# BRD1001-003-320_-_Switchboard.net
KiCad netlist of a schematic drawn in EAGLE
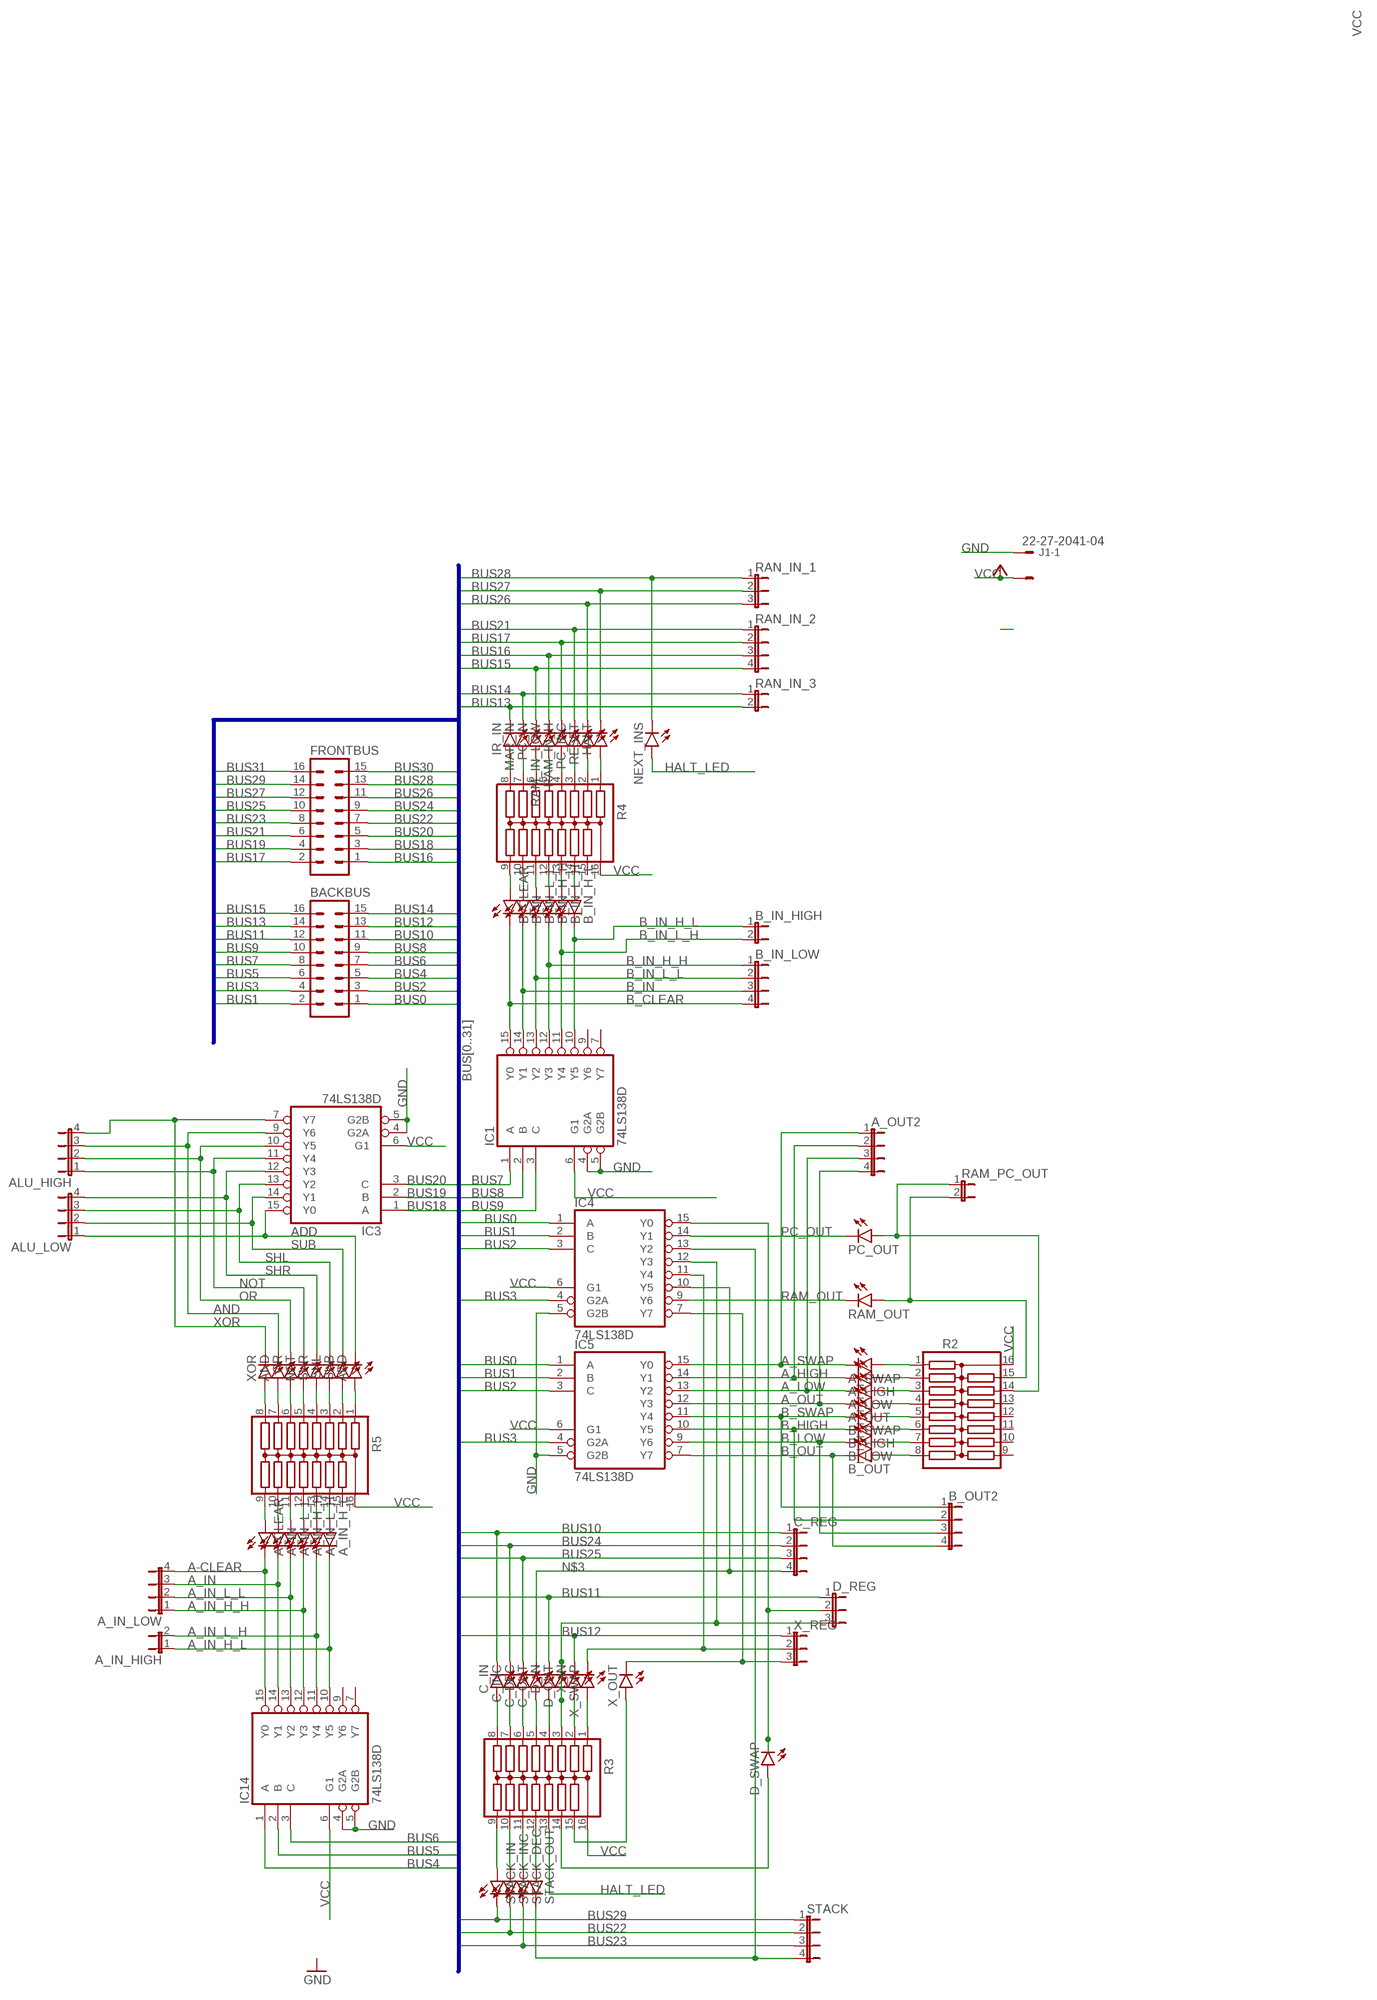
[diagram p0: schematic, sheet 1]

(export (version "E")
  (design (tool "Eeschema 10.0.6"))
  (components
    (comp (ref "ADD")
      (value "LEDSFH482")
      (footprint "eagle-import:SFH482")
      (libsource (lib "eagle-import") (part "LEDSFH482"))
    )
    (comp (ref "ALU_HIGH")
      (value "JP4E")
      (footprint "eagle-import:JP4")
      (libsource (lib "eagle-import") (part "JP4E"))
    )
    (comp (ref "ALU_LOW")
      (value "JP4E")
      (footprint "eagle-import:JP4")
      (libsource (lib "eagle-import") (part "JP4E"))
    )
    (comp (ref "AND")
      (value "LEDSFH482")
      (footprint "eagle-import:SFH482")
      (libsource (lib "eagle-import") (part "LEDSFH482"))
    )
    (comp (ref "A_CLEAR")
      (value "LEDSFH482")
      (footprint "eagle-import:SFH482")
      (libsource (lib "eagle-import") (part "LEDSFH482"))
    )
    (comp (ref "A_HIGH")
      (value "LEDSFH482")
      (footprint "eagle-import:SFH482")
      (libsource (lib "eagle-import") (part "LEDSFH482"))
    )
    (comp (ref "A_IN")
      (value "LEDSFH482")
      (footprint "eagle-import:SFH482")
      (libsource (lib "eagle-import") (part "LEDSFH482"))
    )
    (comp (ref "A_IN_HIGH")
      (value "JP1E")
      (footprint "eagle-import:JP1")
      (libsource (lib "eagle-import") (part "JP1E"))
    )
    (comp (ref "A_IN_H_H")
      (value "LEDSFH482")
      (footprint "eagle-import:SFH482")
      (libsource (lib "eagle-import") (part "LEDSFH482"))
    )
    (comp (ref "A_IN_H_L")
      (value "LEDSFH482")
      (footprint "eagle-import:SFH482")
      (libsource (lib "eagle-import") (part "LEDSFH482"))
    )
    (comp (ref "A_IN_LOW")
      (value "JP4E")
      (footprint "eagle-import:JP4")
      (libsource (lib "eagle-import") (part "JP4E"))
    )
    (comp (ref "A_IN_L_H")
      (value "LEDSFH482")
      (footprint "eagle-import:SFH482")
      (libsource (lib "eagle-import") (part "LEDSFH482"))
    )
    (comp (ref "A_IN_L_L")
      (value "LEDSFH482")
      (footprint "eagle-import:SFH482")
      (libsource (lib "eagle-import") (part "LEDSFH482"))
    )
    (comp (ref "A_LOW")
      (value "LEDSFH482")
      (footprint "eagle-import:SFH482")
      (libsource (lib "eagle-import") (part "LEDSFH482"))
    )
    (comp (ref "A_OUT")
      (value "LEDSFH482")
      (footprint "eagle-import:SFH482")
      (libsource (lib "eagle-import") (part "LEDSFH482"))
    )
    (comp (ref "A_OUT2")
      (value "JP4E")
      (footprint "eagle-import:JP4")
      (libsource (lib "eagle-import") (part "JP4E"))
    )
    (comp (ref "A_SWAP")
      (value "LEDSFH482")
      (footprint "eagle-import:SFH482")
      (libsource (lib "eagle-import") (part "LEDSFH482"))
    )
    (comp (ref "BACKBUS")
      (value "ML16")
      (footprint "eagle-import:ML16")
      (libsource (lib "eagle-import") (part "ML16"))
    )
    (comp (ref "B_CLEAR")
      (value "LEDSFH482")
      (footprint "eagle-import:SFH482")
      (libsource (lib "eagle-import") (part "LEDSFH482"))
    )
    (comp (ref "B_HIGH")
      (value "LEDSFH482")
      (footprint "eagle-import:SFH482")
      (libsource (lib "eagle-import") (part "LEDSFH482"))
    )
    (comp (ref "B_IN")
      (value "LEDSFH482")
      (footprint "eagle-import:SFH482")
      (libsource (lib "eagle-import") (part "LEDSFH482"))
    )
    (comp (ref "B_IN_HIGH")
      (value "JP1E")
      (footprint "eagle-import:JP1")
      (libsource (lib "eagle-import") (part "JP1E"))
    )
    (comp (ref "B_IN_H_H")
      (value "LEDSFH482")
      (footprint "eagle-import:SFH482")
      (libsource (lib "eagle-import") (part "LEDSFH482"))
    )
    (comp (ref "B_IN_H_L")
      (value "LEDSFH482")
      (footprint "eagle-import:SFH482")
      (libsource (lib "eagle-import") (part "LEDSFH482"))
    )
    (comp (ref "B_IN_LOW")
      (value "JP4E")
      (footprint "eagle-import:JP4")
      (libsource (lib "eagle-import") (part "JP4E"))
    )
    (comp (ref "B_IN_L_H")
      (value "LEDSFH482")
      (footprint "eagle-import:SFH482")
      (libsource (lib "eagle-import") (part "LEDSFH482"))
    )
    (comp (ref "B_IN_L_L")
      (value "LEDSFH482")
      (footprint "eagle-import:SFH482")
      (libsource (lib "eagle-import") (part "LEDSFH482"))
    )
    (comp (ref "B_LOW")
      (value "LEDSFH482")
      (footprint "eagle-import:SFH482")
      (libsource (lib "eagle-import") (part "LEDSFH482"))
    )
    (comp (ref "B_OUT")
      (value "LEDSFH482")
      (footprint "eagle-import:SFH482")
      (libsource (lib "eagle-import") (part "LEDSFH482"))
    )
    (comp (ref "B_OUT2")
      (value "JP4E")
      (footprint "eagle-import:JP4")
      (libsource (lib "eagle-import") (part "JP4E"))
    )
    (comp (ref "B_SWAP")
      (value "LEDSFH482")
      (footprint "eagle-import:SFH482")
      (libsource (lib "eagle-import") (part "LEDSFH482"))
    )
    (comp (ref "C_DEC")
      (value "LEDSFH482")
      (footprint "eagle-import:SFH482")
      (libsource (lib "eagle-import") (part "LEDSFH482"))
    )
    (comp (ref "C_IN")
      (value "LEDSFH482")
      (footprint "eagle-import:SFH482")
      (libsource (lib "eagle-import") (part "LEDSFH482"))
    )
    (comp (ref "C_INC")
      (value "LEDSFH482")
      (footprint "eagle-import:SFH482")
      (libsource (lib "eagle-import") (part "LEDSFH482"))
    )
    (comp (ref "C_OUT")
      (value "LEDSFH482")
      (footprint "eagle-import:SFH482")
      (libsource (lib "eagle-import") (part "LEDSFH482"))
    )
    (comp (ref "C_REG")
      (value "JP4E")
      (footprint "eagle-import:JP4")
      (libsource (lib "eagle-import") (part "JP4E"))
    )
    (comp (ref "D_IN")
      (value "LEDSFH482")
      (footprint "eagle-import:SFH482")
      (libsource (lib "eagle-import") (part "LEDSFH482"))
    )
    (comp (ref "D_OUT")
      (value "LEDSFH482")
      (footprint "eagle-import:SFH482")
      (libsource (lib "eagle-import") (part "LEDSFH482"))
    )
    (comp (ref "D_REG")
      (value "JP2W")
      (footprint "eagle-import:JP2W")
      (libsource (lib "eagle-import") (part "JP2W"))
    )
    (comp (ref "D_SWAP")
      (value "LEDSFH482")
      (footprint "eagle-import:SFH482")
      (libsource (lib "eagle-import") (part "LEDSFH482"))
    )
    (comp (ref "FRONTBUS")
      (value "ML16")
      (footprint "eagle-import:ML16")
      (libsource (lib "eagle-import") (part "ML16"))
    )
    (comp (ref "HALT")
      (value "LEDSFH482")
      (footprint "eagle-import:SFH482")
      (libsource (lib "eagle-import") (part "LEDSFH482"))
    )
    (comp (ref "IC1")
      (value "74LS138D")
      (footprint "eagle-import:SO16")
      (libsource (lib "eagle-import") (part "74138DLS"))
    )
    (comp (ref "IC3")
      (value "74LS138D")
      (footprint "eagle-import:SO16")
      (libsource (lib "eagle-import") (part "74138DLS"))
    )
    (comp (ref "IC4")
      (value "74LS138D")
      (footprint "eagle-import:SO16")
      (libsource (lib "eagle-import") (part "74138DLS"))
    )
    (comp (ref "IC5")
      (value "74LS138D")
      (footprint "eagle-import:SO16")
      (libsource (lib "eagle-import") (part "74138DLS"))
    )
    (comp (ref "IC14")
      (value "74LS138D")
      (footprint "eagle-import:SO16")
      (libsource (lib "eagle-import") (part "74138DLS"))
    )
    (comp (ref "IR_IN")
      (value "LEDSFH482")
      (footprint "eagle-import:SFH482")
      (libsource (lib "eagle-import") (part "LEDSFH482"))
    )
    (comp (ref "J1")
      (value "22-27-2041-04")
      (footprint "eagle-import:6410-04")
      (fields (field (name "MF") "MOLEX"))
      (libsource (lib "eagle-import") (part "22-?-0427-2041"))
    )
    (comp (ref "MAR_IN")
      (value "LEDSFH482")
      (footprint "eagle-import:SFH482")
      (libsource (lib "eagle-import") (part "LEDSFH482"))
    )
    (comp (ref "NEXT_INS")
      (value "LEDSFH482")
      (footprint "eagle-import:SFH482")
      (libsource (lib "eagle-import") (part "LEDSFH482"))
    )
    (comp (ref "NOT")
      (value "LEDSFH482")
      (footprint "eagle-import:SFH482")
      (libsource (lib "eagle-import") (part "LEDSFH482"))
    )
    (comp (ref "OR")
      (value "LEDSFH482")
      (footprint "eagle-import:SFH482")
      (libsource (lib "eagle-import") (part "LEDSFH482"))
    )
    (comp (ref "PC_IN")
      (value "LEDSFH482")
      (footprint "eagle-import:SFH482")
      (libsource (lib "eagle-import") (part "LEDSFH482"))
    )
    (comp (ref "PC_INC")
      (value "LEDSFH482")
      (footprint "eagle-import:SFH482")
      (libsource (lib "eagle-import") (part "LEDSFH482"))
    )
    (comp (ref "PC_OUT")
      (value "LEDSFH482")
      (footprint "eagle-import:SFH482")
      (libsource (lib "eagle-import") (part "LEDSFH482"))
    )
    (comp (ref "R2")
      (value "2NBS16-15")
      (footprint "eagle-import:SO16")
      (libsource (lib "eagle-import") (part "2NBS16-15"))
    )
    (comp (ref "R3")
      (value "2NBS16-15")
      (footprint "eagle-import:SO16")
      (libsource (lib "eagle-import") (part "2NBS16-15"))
    )
    (comp (ref "R4")
      (value "2NBS16-15")
      (footprint "eagle-import:SO16")
      (libsource (lib "eagle-import") (part "2NBS16-15"))
    )
    (comp (ref "R5")
      (value "2NBS16-15")
      (footprint "eagle-import:SO16")
      (libsource (lib "eagle-import") (part "2NBS16-15"))
    )
    (comp (ref "RAM_IN_H")
      (value "LEDSFH482")
      (footprint "eagle-import:SFH482")
      (libsource (lib "eagle-import") (part "LEDSFH482"))
    )
    (comp (ref "RAM_IN_LOW")
      (value "LEDSFH482")
      (footprint "eagle-import:SFH482")
      (libsource (lib "eagle-import") (part "LEDSFH482"))
    )
    (comp (ref "RAM_OUT")
      (value "LEDSFH482")
      (footprint "eagle-import:SFH482")
      (libsource (lib "eagle-import") (part "LEDSFH482"))
    )
    (comp (ref "RAM_PC_OUT")
      (value "JP1E")
      (footprint "eagle-import:JP1")
      (libsource (lib "eagle-import") (part "JP1E"))
    )
    (comp (ref "RAN_IN_1")
      (value "JP2W")
      (footprint "eagle-import:JP2W")
      (libsource (lib "eagle-import") (part "JP2W"))
    )
    (comp (ref "RAN_IN_2")
      (value "JP4E")
      (footprint "eagle-import:JP4")
      (libsource (lib "eagle-import") (part "JP4E"))
    )
    (comp (ref "RAN_IN_3")
      (value "JP1E")
      (footprint "eagle-import:JP1")
      (libsource (lib "eagle-import") (part "JP1E"))
    )
    (comp (ref "RESET")
      (value "LEDSFH482")
      (footprint "eagle-import:SFH482")
      (libsource (lib "eagle-import") (part "LEDSFH482"))
    )
    (comp (ref "SHL")
      (value "LEDSFH482")
      (footprint "eagle-import:SFH482")
      (libsource (lib "eagle-import") (part "LEDSFH482"))
    )
    (comp (ref "SHR")
      (value "LEDSFH482")
      (footprint "eagle-import:SFH482")
      (libsource (lib "eagle-import") (part "LEDSFH482"))
    )
    (comp (ref "STACK")
      (value "JP4E")
      (footprint "eagle-import:JP4")
      (libsource (lib "eagle-import") (part "JP4E"))
    )
    (comp (ref "STACK_DEC")
      (value "LEDSFH482")
      (footprint "eagle-import:SFH482")
      (libsource (lib "eagle-import") (part "LEDSFH482"))
    )
    (comp (ref "STACK_IN")
      (value "LEDSFH482")
      (footprint "eagle-import:SFH482")
      (libsource (lib "eagle-import") (part "LEDSFH482"))
    )
    (comp (ref "STACK_INC")
      (value "LEDSFH482")
      (footprint "eagle-import:SFH482")
      (libsource (lib "eagle-import") (part "LEDSFH482"))
    )
    (comp (ref "STACK_OUT")
      (value "LEDSFH482")
      (footprint "eagle-import:SFH482")
      (libsource (lib "eagle-import") (part "LEDSFH482"))
    )
    (comp (ref "SUB")
      (value "LEDSFH482")
      (footprint "eagle-import:SFH482")
      (libsource (lib "eagle-import") (part "LEDSFH482"))
    )
    (comp (ref "XOR")
      (value "LEDSFH482")
      (footprint "eagle-import:SFH482")
      (libsource (lib "eagle-import") (part "LEDSFH482"))
    )
    (comp (ref "X_IN")
      (value "LEDSFH482")
      (footprint "eagle-import:SFH482")
      (libsource (lib "eagle-import") (part "LEDSFH482"))
    )
    (comp (ref "X_OUT")
      (value "LEDSFH482")
      (footprint "eagle-import:SFH482")
      (libsource (lib "eagle-import") (part "LEDSFH482"))
    )
    (comp (ref "X_REG")
      (value "JP2W")
      (footprint "eagle-import:JP2W")
      (libsource (lib "eagle-import") (part "JP2W"))
    )
    (comp (ref "X_SWAP")
      (value "LEDSFH482")
      (footprint "eagle-import:SFH482")
      (libsource (lib "eagle-import") (part "LEDSFH482"))
    )
  )
  (nets
    (net (code "1") (name "/A-CLEAR") (class "Default")
      (node (ref "A_CLEAR") (pin "K") (pinfunction "C_K") (pintype "passive"))
      (node (ref "A_IN_LOW") (pin "4") (pinfunction "4_4") (pintype "passive"))
      (node (ref "IC14") (pin "15") (pinfunction "Y0_15") (pintype "output"))
    )
    (net (code "2") (name "/ADD") (class "Default")
      (node (ref "ADD") (pin "K") (pinfunction "C_K") (pintype "passive"))
      (node (ref "ALU_LOW") (pin "1") (pinfunction "1_1") (pintype "passive"))
      (node (ref "IC3") (pin "15") (pinfunction "Y0_15") (pintype "output"))
    )
    (net (code "3") (name "/AND") (class "Default")
      (node (ref "ALU_HIGH") (pin "3") (pinfunction "3_3") (pintype "passive"))
      (node (ref "AND") (pin "K") (pinfunction "C_K") (pintype "passive"))
      (node (ref "IC3") (pin "9") (pinfunction "Y6_9") (pintype "output"))
    )
    (net (code "4") (name "/A_HIGH") (class "Default")
      (node (ref "A_HIGH") (pin "K") (pinfunction "C_K") (pintype "passive"))
      (node (ref "A_OUT2") (pin "2") (pinfunction "2_2") (pintype "passive"))
      (node (ref "IC5") (pin "14") (pinfunction "Y1_14") (pintype "output"))
    )
    (net (code "5") (name "/A_IN") (class "Default")
      (node (ref "A_IN") (pin "K") (pinfunction "C_K") (pintype "passive"))
      (node (ref "A_IN_LOW") (pin "3") (pinfunction "3_3") (pintype "passive"))
      (node (ref "IC14") (pin "14") (pinfunction "Y1_14") (pintype "output"))
    )
    (net (code "6") (name "/A_IN_H_H") (class "Default")
      (node (ref "A_IN_H_H") (pin "K") (pinfunction "C_K") (pintype "passive"))
      (node (ref "A_IN_LOW") (pin "1") (pinfunction "1_1") (pintype "passive"))
      (node (ref "IC14") (pin "12") (pinfunction "Y3_12") (pintype "output"))
    )
    (net (code "7") (name "/A_IN_H_L") (class "Default")
      (node (ref "A_IN_HIGH") (pin "1") (pinfunction "1_1") (pintype "passive"))
      (node (ref "A_IN_H_L") (pin "K") (pinfunction "C_K") (pintype "passive"))
      (node (ref "IC14") (pin "10") (pinfunction "Y5_10") (pintype "output"))
    )
    (net (code "8") (name "/A_IN_L_H") (class "Default")
      (node (ref "A_IN_HIGH") (pin "2") (pinfunction "2_2") (pintype "passive"))
      (node (ref "A_IN_L_H") (pin "K") (pinfunction "C_K") (pintype "passive"))
      (node (ref "IC14") (pin "11") (pinfunction "Y4_11") (pintype "output"))
    )
    (net (code "9") (name "/A_IN_L_L") (class "Default")
      (node (ref "A_IN_LOW") (pin "2") (pinfunction "2_2") (pintype "passive"))
      (node (ref "A_IN_L_L") (pin "K") (pinfunction "C_K") (pintype "passive"))
      (node (ref "IC14") (pin "13") (pinfunction "Y2_13") (pintype "output"))
    )
    (net (code "10") (name "/A_LOW") (class "Default")
      (node (ref "A_LOW") (pin "K") (pinfunction "C_K") (pintype "passive"))
      (node (ref "A_OUT2") (pin "3") (pinfunction "3_3") (pintype "passive"))
      (node (ref "IC5") (pin "13") (pinfunction "Y2_13") (pintype "output"))
    )
    (net (code "11") (name "/A_OUT") (class "Default")
      (node (ref "A_OUT") (pin "K") (pinfunction "C_K") (pintype "passive"))
      (node (ref "A_OUT2") (pin "4") (pinfunction "4_4") (pintype "passive"))
      (node (ref "IC5") (pin "12") (pinfunction "Y3_12") (pintype "output"))
    )
    (net (code "12") (name "/A_SWAP") (class "Default")
      (node (ref "A_OUT2") (pin "1") (pinfunction "1_1") (pintype "passive"))
      (node (ref "A_SWAP") (pin "K") (pinfunction "C_K") (pintype "passive"))
      (node (ref "IC5") (pin "15") (pinfunction "Y0_15") (pintype "output"))
    )
    (net (code "13") (name "/BUS0") (class "Default")
      (node (ref "BACKBUS") (pin "1") (pinfunction "1_1") (pintype "passive"))
      (node (ref "IC4") (pin "1") (pinfunction "A_1") (pintype "input"))
      (node (ref "IC5") (pin "1") (pinfunction "A_1") (pintype "input"))
    )
    (net (code "14") (name "/BUS1") (class "Default")
      (node (ref "BACKBUS") (pin "2") (pinfunction "2_2") (pintype "passive"))
      (node (ref "IC4") (pin "2") (pinfunction "B_2") (pintype "input"))
      (node (ref "IC5") (pin "2") (pinfunction "B_2") (pintype "input"))
    )
    (net (code "15") (name "/BUS2") (class "Default")
      (node (ref "BACKBUS") (pin "3") (pinfunction "3_3") (pintype "passive"))
      (node (ref "IC4") (pin "3") (pinfunction "C_3") (pintype "input"))
      (node (ref "IC5") (pin "3") (pinfunction "C_3") (pintype "input"))
    )
    (net (code "16") (name "/BUS3") (class "Default")
      (node (ref "BACKBUS") (pin "4") (pinfunction "4_4") (pintype "passive"))
      (node (ref "IC4") (pin "4") (pinfunction "G2A_4") (pintype "input"))
      (node (ref "IC5") (pin "4") (pinfunction "G2A_4") (pintype "input"))
    )
    (net (code "17") (name "/BUS4") (class "Default")
      (node (ref "BACKBUS") (pin "5") (pinfunction "5_5") (pintype "passive"))
      (node (ref "IC14") (pin "1") (pinfunction "A_1") (pintype "input"))
    )
    (net (code "18") (name "/BUS5") (class "Default")
      (node (ref "BACKBUS") (pin "6") (pinfunction "6_6") (pintype "passive"))
      (node (ref "IC14") (pin "2") (pinfunction "B_2") (pintype "input"))
    )
    (net (code "19") (name "/BUS6") (class "Default")
      (node (ref "BACKBUS") (pin "7") (pinfunction "7_7") (pintype "passive"))
      (node (ref "IC14") (pin "3") (pinfunction "C_3") (pintype "input"))
    )
    (net (code "20") (name "/BUS7") (class "Default")
      (node (ref "BACKBUS") (pin "8") (pinfunction "8_8") (pintype "passive"))
      (node (ref "IC1") (pin "1") (pinfunction "A_1") (pintype "input"))
    )
    (net (code "21") (name "/BUS8") (class "Default")
      (node (ref "BACKBUS") (pin "9") (pinfunction "9_9") (pintype "passive"))
      (node (ref "IC1") (pin "2") (pinfunction "B_2") (pintype "input"))
    )
    (net (code "22") (name "/BUS9") (class "Default")
      (node (ref "BACKBUS") (pin "10") (pinfunction "10_10") (pintype "passive"))
      (node (ref "IC1") (pin "3") (pinfunction "C_3") (pintype "input"))
    )
    (net (code "23") (name "/BUS10") (class "Default")
      (node (ref "BACKBUS") (pin "11") (pinfunction "11_11") (pintype "passive"))
      (node (ref "C_IN") (pin "K") (pinfunction "C_K") (pintype "passive"))
      (node (ref "C_REG") (pin "1") (pinfunction "1_1") (pintype "passive"))
    )
    (net (code "24") (name "/BUS11") (class "Default")
      (node (ref "BACKBUS") (pin "12") (pinfunction "12_12") (pintype "passive"))
      (node (ref "D_IN") (pin "K") (pinfunction "C_K") (pintype "passive"))
      (node (ref "D_REG") (pin "1") (pinfunction "1_1") (pintype "passive"))
    )
    (net (code "25") (name "/BUS12") (class "Default")
      (node (ref "BACKBUS") (pin "13") (pinfunction "13_13") (pintype "passive"))
      (node (ref "X_IN") (pin "K") (pinfunction "C_K") (pintype "passive"))
      (node (ref "X_REG") (pin "1") (pinfunction "1_1") (pintype "passive"))
    )
    (net (code "26") (name "/BUS13") (class "Default")
      (node (ref "BACKBUS") (pin "14") (pinfunction "14_14") (pintype "passive"))
      (node (ref "IR_IN") (pin "K") (pinfunction "C_K") (pintype "passive"))
      (node (ref "RAN_IN_3") (pin "2") (pinfunction "2_2") (pintype "passive"))
    )
    (net (code "27") (name "/BUS14") (class "Default")
      (node (ref "BACKBUS") (pin "15") (pinfunction "15_15") (pintype "passive"))
      (node (ref "MAR_IN") (pin "K") (pinfunction "C_K") (pintype "passive"))
      (node (ref "RAN_IN_3") (pin "1") (pinfunction "1_1") (pintype "passive"))
    )
    (net (code "28") (name "/BUS15") (class "Default")
      (node (ref "BACKBUS") (pin "16") (pinfunction "16_16") (pintype "passive"))
      (node (ref "PC_IN") (pin "K") (pinfunction "C_K") (pintype "passive"))
      (node (ref "RAN_IN_2") (pin "4") (pinfunction "4_4") (pintype "passive"))
    )
    (net (code "29") (name "/BUS16") (class "Default")
      (node (ref "FRONTBUS") (pin "1") (pinfunction "1_1") (pintype "passive"))
      (node (ref "RAM_IN_LOW") (pin "K") (pinfunction "C_K") (pintype "passive"))
      (node (ref "RAN_IN_2") (pin "3") (pinfunction "3_3") (pintype "passive"))
    )
    (net (code "30") (name "/BUS17") (class "Default")
      (node (ref "FRONTBUS") (pin "2") (pinfunction "2_2") (pintype "passive"))
      (node (ref "RAM_IN_H") (pin "K") (pinfunction "C_K") (pintype "passive"))
      (node (ref "RAN_IN_2") (pin "2") (pinfunction "2_2") (pintype "passive"))
    )
    (net (code "31") (name "/BUS18") (class "Default")
      (node (ref "FRONTBUS") (pin "3") (pinfunction "3_3") (pintype "passive"))
      (node (ref "IC3") (pin "1") (pinfunction "A_1") (pintype "input"))
    )
    (net (code "32") (name "/BUS19") (class "Default")
      (node (ref "FRONTBUS") (pin "4") (pinfunction "4_4") (pintype "passive"))
      (node (ref "IC3") (pin "2") (pinfunction "B_2") (pintype "input"))
    )
    (net (code "33") (name "/BUS20") (class "Default")
      (node (ref "FRONTBUS") (pin "5") (pinfunction "5_5") (pintype "passive"))
      (node (ref "IC3") (pin "3") (pinfunction "C_3") (pintype "input"))
    )
    (net (code "34") (name "/BUS21") (class "Default")
      (node (ref "FRONTBUS") (pin "6") (pinfunction "6_6") (pintype "passive"))
      (node (ref "PC_INC") (pin "K") (pinfunction "C_K") (pintype "passive"))
      (node (ref "RAN_IN_2") (pin "1") (pinfunction "1_1") (pintype "passive"))
    )
    (net (code "35") (name "/BUS22") (class "Default")
      (node (ref "FRONTBUS") (pin "7") (pinfunction "7_7") (pintype "passive"))
      (node (ref "STACK") (pin "2") (pinfunction "2_2") (pintype "passive"))
      (node (ref "STACK_INC") (pin "K") (pinfunction "C_K") (pintype "passive"))
    )
    (net (code "36") (name "/BUS23") (class "Default")
      (node (ref "FRONTBUS") (pin "8") (pinfunction "8_8") (pintype "passive"))
      (node (ref "STACK") (pin "3") (pinfunction "3_3") (pintype "passive"))
      (node (ref "STACK_DEC") (pin "K") (pinfunction "C_K") (pintype "passive"))
    )
    (net (code "37") (name "/BUS24") (class "Default")
      (node (ref "C_INC") (pin "K") (pinfunction "C_K") (pintype "passive"))
      (node (ref "C_REG") (pin "2") (pinfunction "2_2") (pintype "passive"))
      (node (ref "FRONTBUS") (pin "9") (pinfunction "9_9") (pintype "passive"))
    )
    (net (code "38") (name "/BUS25") (class "Default")
      (node (ref "C_DEC") (pin "K") (pinfunction "C_K") (pintype "passive"))
      (node (ref "C_REG") (pin "3") (pinfunction "3_3") (pintype "passive"))
      (node (ref "FRONTBUS") (pin "10") (pinfunction "10_10") (pintype "passive"))
    )
    (net (code "39") (name "/BUS26") (class "Default")
      (node (ref "FRONTBUS") (pin "11") (pinfunction "11_11") (pintype "passive"))
      (node (ref "RAN_IN_1") (pin "3") (pinfunction "3_3") (pintype "passive"))
      (node (ref "RESET") (pin "K") (pinfunction "C_K") (pintype "passive"))
    )
    (net (code "40") (name "/BUS27") (class "Default")
      (node (ref "FRONTBUS") (pin "12") (pinfunction "12_12") (pintype "passive"))
      (node (ref "HALT") (pin "K") (pinfunction "C_K") (pintype "passive"))
      (node (ref "RAN_IN_1") (pin "2") (pinfunction "2_2") (pintype "passive"))
    )
    (net (code "41") (name "/BUS28") (class "Default")
      (node (ref "FRONTBUS") (pin "13") (pinfunction "13_13") (pintype "passive"))
      (node (ref "NEXT_INS") (pin "K") (pinfunction "C_K") (pintype "passive"))
      (node (ref "RAN_IN_1") (pin "1") (pinfunction "1_1") (pintype "passive"))
    )
    (net (code "42") (name "/BUS29") (class "Default")
      (node (ref "FRONTBUS") (pin "14") (pinfunction "14_14") (pintype "passive"))
      (node (ref "STACK") (pin "1") (pinfunction "1_1") (pintype "passive"))
      (node (ref "STACK_IN") (pin "K") (pinfunction "C_K") (pintype "passive"))
    )
    (net (code "43") (name "/BUS30") (class "Default")
      (node (ref "FRONTBUS") (pin "15") (pinfunction "15_15") (pintype "passive"))
    )
    (net (code "44") (name "/BUS31") (class "Default")
      (node (ref "FRONTBUS") (pin "16") (pinfunction "16_16") (pintype "passive"))
    )
    (net (code "46") (name "/B_CLEAR") (class "Default")
      (node (ref "B_CLEAR") (pin "K") (pinfunction "C_K") (pintype "passive"))
      (node (ref "B_IN_LOW") (pin "4") (pinfunction "4_4") (pintype "passive"))
      (node (ref "IC1") (pin "15") (pinfunction "Y0_15") (pintype "output"))
    )
    (net (code "47") (name "/B_HIGH") (class "Default")
      (node (ref "B_HIGH") (pin "K") (pinfunction "C_K") (pintype "passive"))
      (node (ref "B_OUT2") (pin "2") (pinfunction "2_2") (pintype "passive"))
      (node (ref "IC5") (pin "10") (pinfunction "Y5_10") (pintype "output"))
    )
    (net (code "48") (name "/B_IN") (class "Default")
      (node (ref "B_IN") (pin "K") (pinfunction "C_K") (pintype "passive"))
      (node (ref "B_IN_LOW") (pin "3") (pinfunction "3_3") (pintype "passive"))
      (node (ref "IC1") (pin "14") (pinfunction "Y1_14") (pintype "output"))
    )
    (net (code "49") (name "/B_IN_H_H") (class "Default")
      (node (ref "B_IN_H_H") (pin "K") (pinfunction "C_K") (pintype "passive"))
      (node (ref "B_IN_LOW") (pin "1") (pinfunction "1_1") (pintype "passive"))
      (node (ref "IC1") (pin "12") (pinfunction "Y3_12") (pintype "output"))
    )
    (net (code "50") (name "/B_IN_H_L") (class "Default")
      (node (ref "B_IN_HIGH") (pin "1") (pinfunction "1_1") (pintype "passive"))
      (node (ref "B_IN_H_L") (pin "K") (pinfunction "C_K") (pintype "passive"))
      (node (ref "IC1") (pin "10") (pinfunction "Y5_10") (pintype "output"))
    )
    (net (code "51") (name "/B_IN_L_H") (class "Default")
      (node (ref "B_IN_HIGH") (pin "2") (pinfunction "2_2") (pintype "passive"))
      (node (ref "B_IN_L_H") (pin "K") (pinfunction "C_K") (pintype "passive"))
      (node (ref "IC1") (pin "11") (pinfunction "Y4_11") (pintype "output"))
    )
    (net (code "52") (name "/B_IN_L_L") (class "Default")
      (node (ref "B_IN_LOW") (pin "2") (pinfunction "2_2") (pintype "passive"))
      (node (ref "B_IN_L_L") (pin "K") (pinfunction "C_K") (pintype "passive"))
      (node (ref "IC1") (pin "13") (pinfunction "Y2_13") (pintype "output"))
    )
    (net (code "53") (name "/B_LOW") (class "Default")
      (node (ref "B_LOW") (pin "K") (pinfunction "C_K") (pintype "passive"))
      (node (ref "B_OUT2") (pin "3") (pinfunction "3_3") (pintype "passive"))
      (node (ref "IC5") (pin "9") (pinfunction "Y6_9") (pintype "output"))
    )
    (net (code "54") (name "/B_OUT") (class "Default")
      (node (ref "B_OUT") (pin "K") (pinfunction "C_K") (pintype "passive"))
      (node (ref "B_OUT2") (pin "4") (pinfunction "4_4") (pintype "passive"))
      (node (ref "IC5") (pin "7") (pinfunction "Y7_7") (pintype "output"))
    )
    (net (code "55") (name "/B_SWAP") (class "Default")
      (node (ref "B_OUT2") (pin "1") (pinfunction "1_1") (pintype "passive"))
      (node (ref "B_SWAP") (pin "K") (pinfunction "C_K") (pintype "passive"))
      (node (ref "IC5") (pin "11") (pinfunction "Y4_11") (pintype "output"))
    )
    (net (code "56") (name "/HALT_LED") (class "Default")
      (node (ref "NEXT_INS") (pin "A") (pinfunction "A_A") (pintype "passive"))
      (node (ref "R3") (pin "13") (pinfunction "13_13") (pintype "passive"))
    )
    (net (code "57") (name "/N$3") (class "Default")
      (node (ref "C_OUT") (pin "K") (pinfunction "C_K") (pintype "passive"))
      (node (ref "C_REG") (pin "4") (pinfunction "4_4") (pintype "passive"))
      (node (ref "IC4") (pin "10") (pinfunction "Y5_10") (pintype "output"))
    )
    (net (code "58") (name "/NOT") (class "Default")
      (node (ref "ALU_HIGH") (pin "1") (pinfunction "1_1") (pintype "passive"))
      (node (ref "IC3") (pin "11") (pinfunction "Y4_11") (pintype "output"))
      (node (ref "NOT") (pin "K") (pinfunction "C_K") (pintype "passive"))
    )
    (net (code "59") (name "/OR") (class "Default")
      (node (ref "ALU_HIGH") (pin "2") (pinfunction "2_2") (pintype "passive"))
      (node (ref "IC3") (pin "10") (pinfunction "Y5_10") (pintype "output"))
      (node (ref "OR") (pin "K") (pinfunction "C_K") (pintype "passive"))
    )
    (net (code "60") (name "/PC_OUT") (class "Default")
      (node (ref "IC4") (pin "14") (pinfunction "Y1_14") (pintype "output"))
      (node (ref "PC_OUT") (pin "K") (pinfunction "C_K") (pintype "passive"))
    )
    (net (code "61") (name "/RAM_OUT") (class "Default")
      (node (ref "IC4") (pin "9") (pinfunction "Y6_9") (pintype "output"))
      (node (ref "RAM_OUT") (pin "K") (pinfunction "C_K") (pintype "passive"))
    )
    (net (code "62") (name "/SHL") (class "Default")
      (node (ref "ALU_LOW") (pin "3") (pinfunction "3_3") (pintype "passive"))
      (node (ref "IC3") (pin "13") (pinfunction "Y2_13") (pintype "output"))
      (node (ref "SHL") (pin "K") (pinfunction "C_K") (pintype "passive"))
    )
    (net (code "63") (name "/SHR") (class "Default")
      (node (ref "ALU_LOW") (pin "4") (pinfunction "4_4") (pintype "passive"))
      (node (ref "IC3") (pin "12") (pinfunction "Y3_12") (pintype "output"))
      (node (ref "SHR") (pin "K") (pinfunction "C_K") (pintype "passive"))
    )
    (net (code "64") (name "/SUB") (class "Default")
      (node (ref "ALU_LOW") (pin "2") (pinfunction "2_2") (pintype "passive"))
      (node (ref "IC3") (pin "14") (pinfunction "Y1_14") (pintype "output"))
      (node (ref "SUB") (pin "K") (pinfunction "C_K") (pintype "passive"))
    )
    (net (code "65") (name "/XOR") (class "Default")
      (node (ref "ALU_HIGH") (pin "4") (pinfunction "4_4") (pintype "passive"))
      (node (ref "IC3") (pin "7") (pinfunction "Y7_7") (pintype "output"))
      (node (ref "XOR") (pin "K") (pinfunction "C_K") (pintype "passive"))
    )
    (net (code "66") (name "GND") (class "Default")
      (node (ref "IC1") (pin "4") (pinfunction "G2A_4") (pintype "input"))
      (node (ref "IC1") (pin "5") (pinfunction "G2B_5") (pintype "input"))
      (node (ref "IC14") (pin "4") (pinfunction "G2A_4") (pintype "input"))
      (node (ref "IC14") (pin "5") (pinfunction "G2B_5") (pintype "input"))
      (node (ref "IC3") (pin "4") (pinfunction "G2A_4") (pintype "input"))
      (node (ref "IC3") (pin "5") (pinfunction "G2B_5") (pintype "input"))
      (node (ref "IC4") (pin "5") (pinfunction "G2B_5") (pintype "input"))
      (node (ref "IC5") (pin "5") (pinfunction "G2B_5") (pintype "input"))
      (node (ref "J1") (pin "1") (pinfunction "S_1") (pintype "passive"))
    )
    (net (code "67") (name "Net-(ADD-PadA)") (class "Default")
      (node (ref "ADD") (pin "A") (pinfunction "A_A") (pintype "passive"))
      (node (ref "R5") (pin "1") (pinfunction "1_1") (pintype "passive"))
    )
    (net (code "68") (name "Net-(AND-PadA)") (class "Default")
      (node (ref "AND") (pin "A") (pinfunction "A_A") (pintype "passive"))
      (node (ref "R5") (pin "7") (pinfunction "7_7") (pintype "passive"))
    )
    (net (code "69") (name "Net-(A_CLEAR-PadA)") (class "Default")
      (node (ref "A_CLEAR") (pin "A") (pinfunction "A_A") (pintype "passive"))
      (node (ref "R5") (pin "9") (pinfunction "9_9") (pintype "passive"))
    )
    (net (code "70") (name "Net-(A_HIGH-PadA)") (class "Default")
      (node (ref "A_HIGH") (pin "A") (pinfunction "A_A") (pintype "passive"))
      (node (ref "R2") (pin "2") (pinfunction "2_2") (pintype "passive"))
    )
    (net (code "71") (name "Net-(A_IN-PadA)") (class "Default")
      (node (ref "A_IN") (pin "A") (pinfunction "A_A") (pintype "passive"))
      (node (ref "R5") (pin "10") (pinfunction "10_10") (pintype "passive"))
    )
    (net (code "72") (name "Net-(A_IN_H_H-PadA)") (class "Default")
      (node (ref "A_IN_H_H") (pin "A") (pinfunction "A_A") (pintype "passive"))
      (node (ref "R5") (pin "12") (pinfunction "12_12") (pintype "passive"))
    )
    (net (code "73") (name "Net-(A_IN_H_L-PadA)") (class "Default")
      (node (ref "A_IN_H_L") (pin "A") (pinfunction "A_A") (pintype "passive"))
      (node (ref "R5") (pin "14") (pinfunction "14_14") (pintype "passive"))
    )
    (net (code "74") (name "Net-(A_IN_L_H-PadA)") (class "Default")
      (node (ref "A_IN_L_H") (pin "A") (pinfunction "A_A") (pintype "passive"))
      (node (ref "R5") (pin "13") (pinfunction "13_13") (pintype "passive"))
    )
    (net (code "75") (name "Net-(A_IN_L_L-PadA)") (class "Default")
      (node (ref "A_IN_L_L") (pin "A") (pinfunction "A_A") (pintype "passive"))
      (node (ref "R5") (pin "11") (pinfunction "11_11") (pintype "passive"))
    )
    (net (code "76") (name "Net-(A_LOW-PadA)") (class "Default")
      (node (ref "A_LOW") (pin "A") (pinfunction "A_A") (pintype "passive"))
      (node (ref "R2") (pin "3") (pinfunction "3_3") (pintype "passive"))
    )
    (net (code "77") (name "Net-(A_OUT-PadA)") (class "Default")
      (node (ref "A_OUT") (pin "A") (pinfunction "A_A") (pintype "passive"))
      (node (ref "R2") (pin "4") (pinfunction "4_4") (pintype "passive"))
    )
    (net (code "78") (name "Net-(A_SWAP-PadA)") (class "Default")
      (node (ref "A_SWAP") (pin "A") (pinfunction "A_A") (pintype "passive"))
      (node (ref "R2") (pin "1") (pinfunction "1_1") (pintype "passive"))
    )
    (net (code "79") (name "Net-(B_CLEAR-PadA)") (class "Default")
      (node (ref "B_CLEAR") (pin "A") (pinfunction "A_A") (pintype "passive"))
      (node (ref "R4") (pin "9") (pinfunction "9_9") (pintype "passive"))
    )
    (net (code "80") (name "Net-(B_HIGH-PadA)") (class "Default")
      (node (ref "B_HIGH") (pin "A") (pinfunction "A_A") (pintype "passive"))
      (node (ref "R2") (pin "6") (pinfunction "6_6") (pintype "passive"))
    )
    (net (code "81") (name "Net-(B_IN-PadA)") (class "Default")
      (node (ref "B_IN") (pin "A") (pinfunction "A_A") (pintype "passive"))
      (node (ref "R4") (pin "10") (pinfunction "10_10") (pintype "passive"))
    )
    (net (code "82") (name "Net-(B_IN_H_H-PadA)") (class "Default")
      (node (ref "B_IN_H_H") (pin "A") (pinfunction "A_A") (pintype "passive"))
      (node (ref "R4") (pin "12") (pinfunction "12_12") (pintype "passive"))
    )
    (net (code "83") (name "Net-(B_IN_H_L-PadA)") (class "Default")
      (node (ref "B_IN_H_L") (pin "A") (pinfunction "A_A") (pintype "passive"))
      (node (ref "R4") (pin "14") (pinfunction "14_14") (pintype "passive"))
    )
    (net (code "84") (name "Net-(B_IN_L_H-PadA)") (class "Default")
      (node (ref "B_IN_L_H") (pin "A") (pinfunction "A_A") (pintype "passive"))
      (node (ref "R4") (pin "13") (pinfunction "13_13") (pintype "passive"))
    )
    (net (code "85") (name "Net-(B_IN_L_L-PadA)") (class "Default")
      (node (ref "B_IN_L_L") (pin "A") (pinfunction "A_A") (pintype "passive"))
      (node (ref "R4") (pin "11") (pinfunction "11_11") (pintype "passive"))
    )
    (net (code "86") (name "Net-(B_LOW-PadA)") (class "Default")
      (node (ref "B_LOW") (pin "A") (pinfunction "A_A") (pintype "passive"))
      (node (ref "R2") (pin "7") (pinfunction "7_7") (pintype "passive"))
    )
    (net (code "87") (name "Net-(B_OUT-PadA)") (class "Default")
      (node (ref "B_OUT") (pin "A") (pinfunction "A_A") (pintype "passive"))
      (node (ref "R2") (pin "8") (pinfunction "8_8") (pintype "passive"))
    )
    (net (code "88") (name "Net-(B_SWAP-PadA)") (class "Default")
      (node (ref "B_SWAP") (pin "A") (pinfunction "A_A") (pintype "passive"))
      (node (ref "R2") (pin "5") (pinfunction "5_5") (pintype "passive"))
    )
    (net (code "89") (name "Net-(C_DEC-PadA)") (class "Default")
      (node (ref "C_DEC") (pin "A") (pinfunction "A_A") (pintype "passive"))
      (node (ref "R3") (pin "6") (pinfunction "6_6") (pintype "passive"))
    )
    (net (code "90") (name "Net-(C_IN-PadA)") (class "Default")
      (node (ref "C_IN") (pin "A") (pinfunction "A_A") (pintype "passive"))
      (node (ref "R3") (pin "8") (pinfunction "8_8") (pintype "passive"))
    )
    (net (code "91") (name "Net-(C_INC-PadA)") (class "Default")
      (node (ref "C_INC") (pin "A") (pinfunction "A_A") (pintype "passive"))
      (node (ref "R3") (pin "7") (pinfunction "7_7") (pintype "passive"))
    )
    (net (code "92") (name "Net-(C_OUT-PadA)") (class "Default")
      (node (ref "C_OUT") (pin "A") (pinfunction "A_A") (pintype "passive"))
      (node (ref "R3") (pin "5") (pinfunction "5_5") (pintype "passive"))
    )
    (net (code "93") (name "Net-(D_IN-PadA)") (class "Default")
      (node (ref "D_IN") (pin "A") (pinfunction "A_A") (pintype "passive"))
      (node (ref "R3") (pin "4") (pinfunction "4_4") (pintype "passive"))
    )
    (net (code "94") (name "Net-(D_OUT-C)") (class "Default")
      (node (ref "D_OUT") (pin "A") (pinfunction "A_A") (pintype "passive"))
      (node (ref "D_OUT") (pin "K") (pinfunction "C_K") (pintype "passive"))
      (node (ref "D_REG") (pin "3") (pinfunction "3_3") (pintype "passive"))
      (node (ref "IC4") (pin "12") (pinfunction "Y3_12") (pintype "output"))
      (node (ref "R3") (pin "3") (pinfunction "3_3") (pintype "passive"))
    )
    (net (code "95") (name "Net-(D_SWAP-C)") (class "Default")
      (node (ref "D_REG") (pin "2") (pinfunction "2_2") (pintype "passive"))
      (node (ref "D_SWAP") (pin "K") (pinfunction "C_K") (pintype "passive"))
      (node (ref "IC4") (pin "15") (pinfunction "Y0_15") (pintype "output"))
    )
    (net (code "96") (name "Net-(D_SWAP-PadA)") (class "Default")
      (node (ref "D_SWAP") (pin "A") (pinfunction "A_A") (pintype "passive"))
      (node (ref "R3") (pin "14") (pinfunction "14_14") (pintype "passive"))
    )
    (net (code "97") (name "Net-(HALT-PadA)") (class "Default")
      (node (ref "HALT") (pin "A") (pinfunction "A_A") (pintype "passive"))
      (node (ref "R4") (pin "1") (pinfunction "1_1") (pintype "passive"))
    )
    (net (code "98") (name "Net-(IC4A-Y2)") (class "Default")
      (node (ref "IC4") (pin "13") (pinfunction "Y2_13") (pintype "output"))
      (node (ref "STACK") (pin "4") (pinfunction "4_4") (pintype "passive"))
      (node (ref "STACK_OUT") (pin "K") (pinfunction "C_K") (pintype "passive"))
    )
    (net (code "99") (name "Net-(IC4A-Y4)") (class "Default")
      (node (ref "IC4") (pin "11") (pinfunction "Y4_11") (pintype "output"))
      (node (ref "X_REG") (pin "2") (pinfunction "2_2") (pintype "passive"))
      (node (ref "X_SWAP") (pin "K") (pinfunction "C_K") (pintype "passive"))
    )
    (net (code "100") (name "Net-(IC4A-Y7)") (class "Default")
      (node (ref "IC4") (pin "7") (pinfunction "Y7_7") (pintype "output"))
      (node (ref "X_OUT") (pin "K") (pinfunction "C_K") (pintype "passive"))
      (node (ref "X_REG") (pin "3") (pinfunction "3_3") (pintype "passive"))
    )
    (net (code "101") (name "Net-(IR_IN-PadA)") (class "Default")
      (node (ref "IR_IN") (pin "A") (pinfunction "A_A") (pintype "passive"))
      (node (ref "R4") (pin "8") (pinfunction "8_8") (pintype "passive"))
    )
    (net (code "102") (name "Net-(MAR_IN-PadA)") (class "Default")
      (node (ref "MAR_IN") (pin "A") (pinfunction "A_A") (pintype "passive"))
      (node (ref "R4") (pin "7") (pinfunction "7_7") (pintype "passive"))
    )
    (net (code "103") (name "Net-(NOT-PadA)") (class "Default")
      (node (ref "NOT") (pin "A") (pinfunction "A_A") (pintype "passive"))
      (node (ref "R5") (pin "5") (pinfunction "5_5") (pintype "passive"))
    )
    (net (code "104") (name "Net-(OR-PadA)") (class "Default")
      (node (ref "OR") (pin "A") (pinfunction "A_A") (pintype "passive"))
      (node (ref "R5") (pin "6") (pinfunction "6_6") (pintype "passive"))
    )
    (net (code "105") (name "Net-(PC_IN-PadA)") (class "Default")
      (node (ref "PC_IN") (pin "A") (pinfunction "A_A") (pintype "passive"))
      (node (ref "R4") (pin "6") (pinfunction "6_6") (pintype "passive"))
    )
    (net (code "106") (name "Net-(PC_INC-PadA)") (class "Default")
      (node (ref "PC_INC") (pin "A") (pinfunction "A_A") (pintype "passive"))
      (node (ref "R4") (pin "3") (pinfunction "3_3") (pintype "passive"))
    )
    (net (code "107") (name "Net-(PC_OUT-PadA)") (class "Default")
      (node (ref "PC_OUT") (pin "A") (pinfunction "A_A") (pintype "passive"))
      (node (ref "R2") (pin "14") (pinfunction "14_14") (pintype "passive"))
      (node (ref "RAM_PC_OUT") (pin "1") (pinfunction "1_1") (pintype "passive"))
    )
    (net (code "108") (name "Net-(R2-Pad15)") (class "Default")
      (node (ref "R2") (pin "15") (pinfunction "15_15") (pintype "passive"))
      (node (ref "RAM_OUT") (pin "A") (pinfunction "A_A") (pintype "passive"))
      (node (ref "RAM_PC_OUT") (pin "2") (pinfunction "2_2") (pintype "passive"))
    )
    (net (code "109") (name "Net-(R3-Pad1)") (class "Default")
      (node (ref "R3") (pin "1") (pinfunction "1_1") (pintype "passive"))
      (node (ref "X_SWAP") (pin "A") (pinfunction "A_A") (pintype "passive"))
    )
    (net (code "110") (name "Net-(R3-Pad2)") (class "Default")
      (node (ref "R3") (pin "2") (pinfunction "2_2") (pintype "passive"))
      (node (ref "X_IN") (pin "A") (pinfunction "A_A") (pintype "passive"))
    )
    (net (code "111") (name "Net-(R3-Pad9)") (class "Default")
      (node (ref "R3") (pin "9") (pinfunction "9_9") (pintype "passive"))
      (node (ref "STACK_IN") (pin "A") (pinfunction "A_A") (pintype "passive"))
    )
    (net (code "112") (name "Net-(R3-Pad10)") (class "Default")
      (node (ref "R3") (pin "10") (pinfunction "10_10") (pintype "passive"))
      (node (ref "STACK_INC") (pin "A") (pinfunction "A_A") (pintype "passive"))
    )
    (net (code "113") (name "Net-(R3-Pad11)") (class "Default")
      (node (ref "R3") (pin "11") (pinfunction "11_11") (pintype "passive"))
      (node (ref "STACK_DEC") (pin "A") (pinfunction "A_A") (pintype "passive"))
    )
    (net (code "114") (name "Net-(R3-Pad12)") (class "Default")
      (node (ref "R3") (pin "12") (pinfunction "12_12") (pintype "passive"))
      (node (ref "STACK_OUT") (pin "A") (pinfunction "A_A") (pintype "passive"))
    )
    (net (code "115") (name "Net-(R3-Pad15)") (class "Default")
      (node (ref "R3") (pin "15") (pinfunction "15_15") (pintype "passive"))
      (node (ref "X_OUT") (pin "A") (pinfunction "A_A") (pintype "passive"))
    )
    (net (code "116") (name "Net-(R4-Pad2)") (class "Default")
      (node (ref "R4") (pin "2") (pinfunction "2_2") (pintype "passive"))
      (node (ref "RESET") (pin "A") (pinfunction "A_A") (pintype "passive"))
    )
    (net (code "117") (name "Net-(R4-Pad4)") (class "Default")
      (node (ref "R4") (pin "4") (pinfunction "4_4") (pintype "passive"))
      (node (ref "RAM_IN_H") (pin "A") (pinfunction "A_A") (pintype "passive"))
    )
    (net (code "118") (name "Net-(R4-Pad5)") (class "Default")
      (node (ref "R4") (pin "5") (pinfunction "5_5") (pintype "passive"))
      (node (ref "RAM_IN_LOW") (pin "A") (pinfunction "A_A") (pintype "passive"))
    )
    (net (code "119") (name "Net-(R5-Pad2)") (class "Default")
      (node (ref "R5") (pin "2") (pinfunction "2_2") (pintype "passive"))
      (node (ref "SUB") (pin "A") (pinfunction "A_A") (pintype "passive"))
    )
    (net (code "120") (name "Net-(R5-Pad3)") (class "Default")
      (node (ref "R5") (pin "3") (pinfunction "3_3") (pintype "passive"))
      (node (ref "SHL") (pin "A") (pinfunction "A_A") (pintype "passive"))
    )
    (net (code "121") (name "Net-(R5-Pad4)") (class "Default")
      (node (ref "R5") (pin "4") (pinfunction "4_4") (pintype "passive"))
      (node (ref "SHR") (pin "A") (pinfunction "A_A") (pintype "passive"))
    )
    (net (code "122") (name "Net-(R5-Pad8)") (class "Default")
      (node (ref "R5") (pin "8") (pinfunction "8_8") (pintype "passive"))
      (node (ref "XOR") (pin "A") (pinfunction "A_A") (pintype "passive"))
    )
    (net (code "123") (name "VCC") (class "Default")
      (node (ref "IC1") (pin "6") (pinfunction "G1_6") (pintype "input"))
      (node (ref "IC14") (pin "6") (pinfunction "G1_6") (pintype "input"))
      (node (ref "IC3") (pin "6") (pinfunction "G1_6") (pintype "input"))
      (node (ref "IC4") (pin "6") (pinfunction "G1_6") (pintype "input"))
      (node (ref "IC5") (pin "6") (pinfunction "G1_6") (pintype "input"))
      (node (ref "J1") (pin "2") (pinfunction "S_2") (pintype "passive"))
      (node (ref "R2") (pin "16") (pinfunction "16_16") (pintype "passive"))
      (node (ref "R3") (pin "16") (pinfunction "16_16") (pintype "passive"))
      (node (ref "R4") (pin "16") (pinfunction "16_16") (pintype "passive"))
      (node (ref "R5") (pin "16") (pinfunction "16_16") (pintype "passive"))
    )
    (net (code "124") (name "unconnected-(IC1A-Y6-Pad9)") (class "Default")
      (node (ref "IC1") (pin "9") (pinfunction "Y6_9") (pintype "output"))
    )
    (net (code "125") (name "unconnected-(IC1A-Y7-Pad7)") (class "Default")
      (node (ref "IC1") (pin "7") (pinfunction "Y7_7") (pintype "output"))
    )
    (net (code "126") (name "unconnected-(IC14A-Y6-Pad9)") (class "Default")
      (node (ref "IC14") (pin "9") (pinfunction "Y6_9") (pintype "output"))
    )
    (net (code "127") (name "unconnected-(IC14A-Y7-Pad7)") (class "Default")
      (node (ref "IC14") (pin "7") (pinfunction "Y7_7") (pintype "output"))
    )
    (net (code "128") (name "unconnected-(R2-Pad9)") (class "Default")
      (node (ref "R2") (pin "9") (pinfunction "9_9") (pintype "passive"))
    )
    (net (code "129") (name "unconnected-(R2-Pad10)") (class "Default")
      (node (ref "R2") (pin "10") (pinfunction "10_10") (pintype "passive"))
    )
    (net (code "130") (name "unconnected-(R2-Pad11)") (class "Default")
      (node (ref "R2") (pin "11") (pinfunction "11_11") (pintype "passive"))
    )
    (net (code "131") (name "unconnected-(R2-Pad12)") (class "Default")
      (node (ref "R2") (pin "12") (pinfunction "12_12") (pintype "passive"))
    )
    (net (code "132") (name "unconnected-(R2-Pad13)") (class "Default")
      (node (ref "R2") (pin "13") (pinfunction "13_13") (pintype "passive"))
    )
    (net (code "133") (name "unconnected-(R4-Pad15)") (class "Default")
      (node (ref "R4") (pin "15") (pinfunction "15_15") (pintype "passive"))
    )
    (net (code "134") (name "unconnected-(R5-Pad15)") (class "Default")
      (node (ref "R5") (pin "15") (pinfunction "15_15") (pintype "passive"))
    )
  )
)
